# controller11lcd.net
KiCad netlist of a schematic drawn in EAGLE
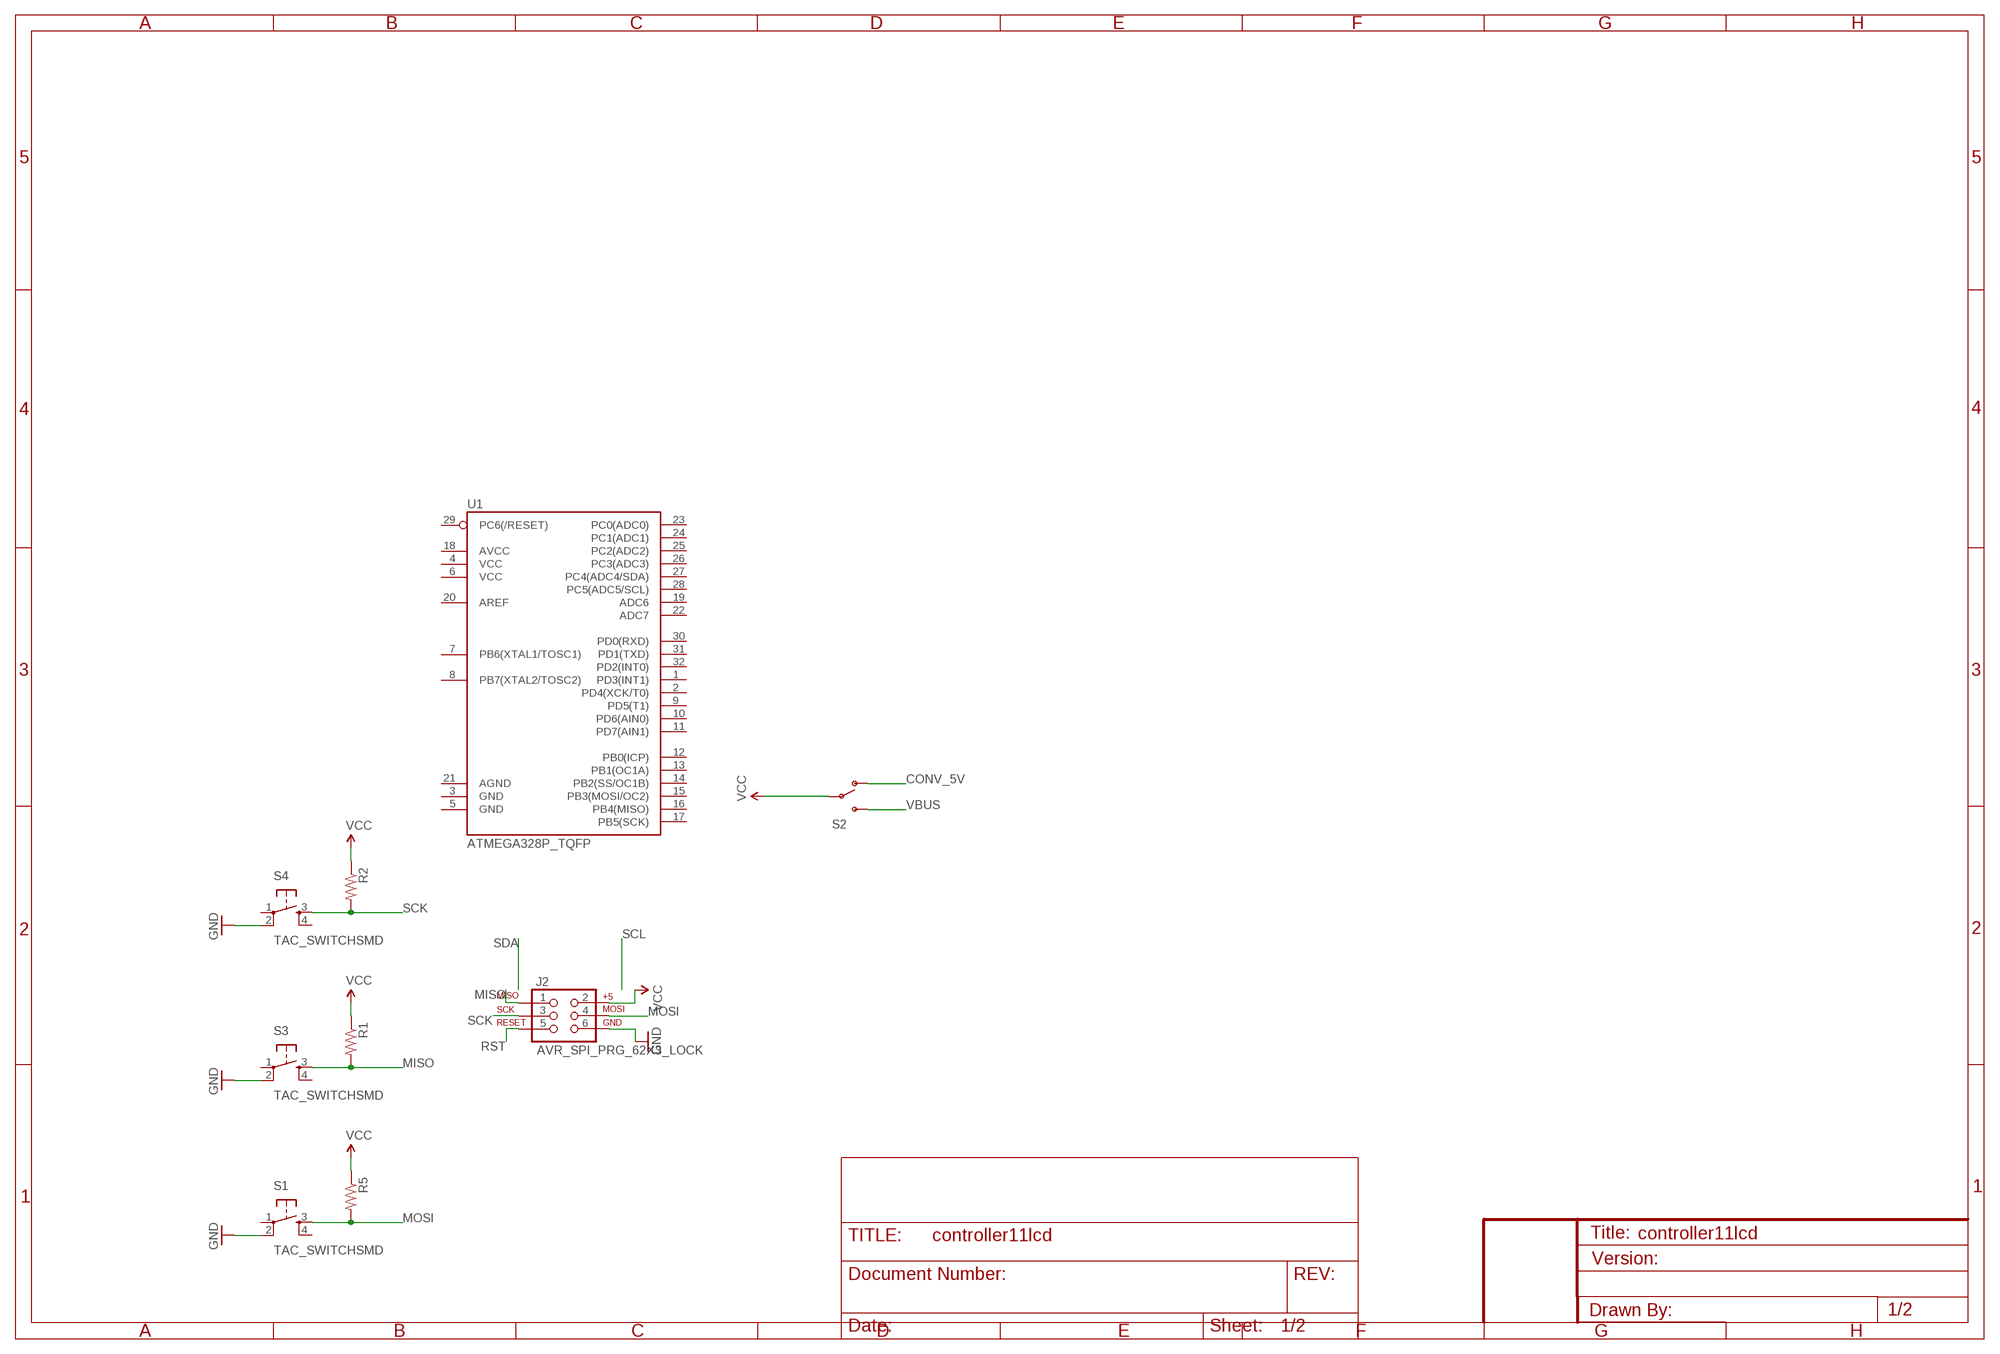
[diagram p0: schematic, sheet 1]
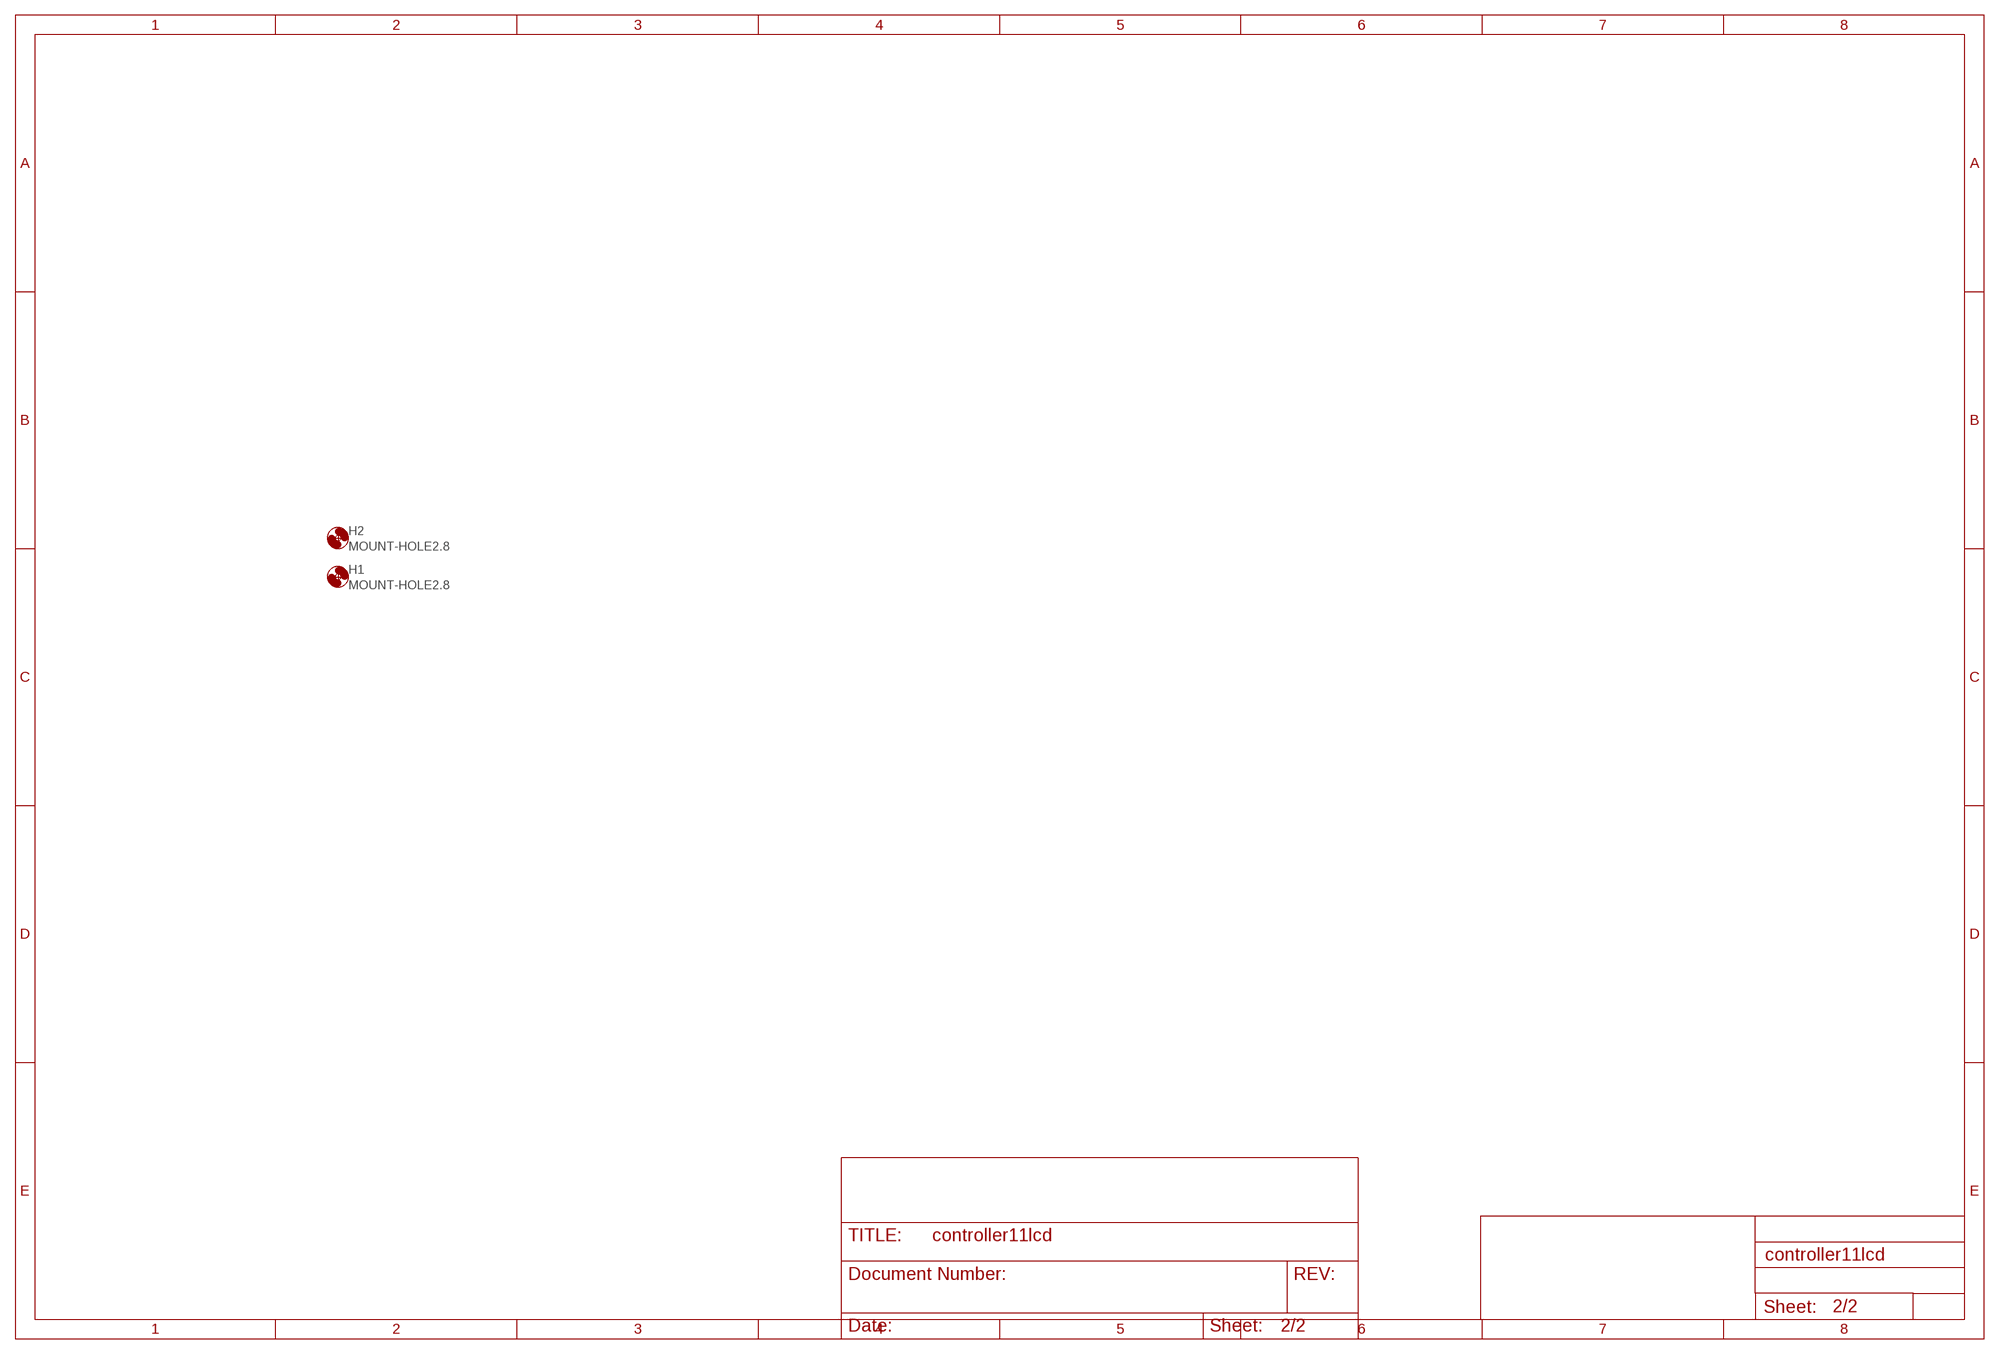
[diagram p1: schematic, sheet 2]

(export (version "E")
  (design (tool "Eeschema 10.0.6"))
  (components
    (comp (ref "H1")
      (value "MOUNT-HOLE2.8")
      (footprint "eagle-import:2,8")
      (libsource (lib "eagle-import") (part "MOUNT-HOLE2.8"))
    )
    (comp (ref "H2")
      (value "MOUNT-HOLE2.8")
      (footprint "eagle-import:2,8")
      (libsource (lib "eagle-import") (part "MOUNT-HOLE2.8"))
    )
    (comp (ref "J2")
      (value "AVR_SPI_PRG_62X3_LOCK")
      (footprint "eagle-import:2X3_LOCK")
      (libsource (lib "eagle-import") (part "AVR_SPI_PRG_62X3_LOCK"))
    )
    (comp (ref "R1")
      (value "RESISTOR1206")
      (footprint "eagle-import:1206")
      (libsource (lib "eagle-import") (part "RESISTOR1206"))
    )
    (comp (ref "R2")
      (value "RESISTOR1206")
      (footprint "eagle-import:1206")
      (libsource (lib "eagle-import") (part "RESISTOR1206"))
    )
    (comp (ref "R5")
      (value "RESISTOR1206")
      (footprint "eagle-import:1206")
      (libsource (lib "eagle-import") (part "RESISTOR1206"))
    )
    (comp (ref "S1")
      (value "TAC_SWITCHSMD")
      (footprint "eagle-import:TACTILE-PTH")
      (libsource (lib "eagle-import") (part "TAC_SWITCHPTH"))
    )
    (comp (ref "S2")
      (value "SWITCH-SPDTSMD2")
      (footprint "eagle-import:SWITCH-SPDT-SMD")
      (libsource (lib "eagle-import") (part "SWITCH-SPDTSMD2"))
    )
    (comp (ref "S3")
      (value "TAC_SWITCHSMD")
      (footprint "eagle-import:TACTILE-PTH")
      (libsource (lib "eagle-import") (part "TAC_SWITCHPTH"))
    )
    (comp (ref "S4")
      (value "TAC_SWITCHSMD")
      (footprint "eagle-import:TACTILE-PTH")
      (libsource (lib "eagle-import") (part "TAC_SWITCHPTH"))
    )
    (comp (ref "U1")
      (value "ATMEGA328P_TQFP")
      (footprint "eagle-import:TQFP32-08")
      (libsource (lib "eagle-import") (part "ATMEGA328P_TQFP"))
    )
  )
  (nets
    (net (code "1") (name "CONV_5V") (class "Default")
      (node (ref "S2") (pin "1") (pinfunction "O_1") (pintype "passive"))
    )
    (net (code "2") (name "GND") (class "Default")
      (node (ref "J2") (pin "6") (pinfunction "6_6") (pintype "passive"))
      (node (ref "S1") (pin "2") (pinfunction "2_2") (pintype "passive"))
      (node (ref "S3") (pin "2") (pinfunction "2_2") (pintype "passive"))
      (node (ref "S4") (pin "2") (pinfunction "2_2") (pintype "passive"))
    )
    (net (code "3") (name "MISO") (class "Default")
      (node (ref "J2") (pin "1") (pinfunction "1_1") (pintype "passive"))
      (node (ref "R1") (pin "2") (pinfunction "2_2") (pintype "passive"))
      (node (ref "S3") (pin "3") (pinfunction "3_3") (pintype "passive"))
    )
    (net (code "4") (name "MOSI") (class "Default")
      (node (ref "J2") (pin "4") (pinfunction "4_4") (pintype "passive"))
      (node (ref "R5") (pin "2") (pinfunction "2_2") (pintype "passive"))
      (node (ref "S1") (pin "3") (pinfunction "3_3") (pintype "passive"))
    )
    (net (code "5") (name "RST") (class "Default")
      (node (ref "J2") (pin "5") (pinfunction "5_5") (pintype "passive"))
    )
    (net (code "6") (name "SCK") (class "Default")
      (node (ref "J2") (pin "3") (pinfunction "3_3") (pintype "passive"))
      (node (ref "R2") (pin "2") (pinfunction "2_2") (pintype "passive"))
      (node (ref "S4") (pin "3") (pinfunction "3_3") (pintype "passive"))
    )
    (net (code "9") (name "VBUS") (class "Default")
      (node (ref "S2") (pin "3") (pinfunction "S_3") (pintype "passive"))
    )
    (net (code "10") (name "VCC") (class "Default")
      (node (ref "J2") (pin "2") (pinfunction "2_2") (pintype "passive"))
      (node (ref "R1") (pin "1") (pinfunction "1_1") (pintype "passive"))
      (node (ref "R2") (pin "1") (pinfunction "1_1") (pintype "passive"))
      (node (ref "R5") (pin "1") (pinfunction "1_1") (pintype "passive"))
      (node (ref "S2") (pin "2") (pinfunction "P_2") (pintype "passive"))
    )
    (net (code "11") (name "unconnected-(S1-Pad1)") (class "Default")
      (node (ref "S1") (pin "1") (pinfunction "1_1") (pintype "passive"))
    )
    (net (code "12") (name "unconnected-(S1-Pad4)") (class "Default")
      (node (ref "S1") (pin "4") (pinfunction "4_4") (pintype "passive"))
    )
    (net (code "13") (name "unconnected-(S3-Pad1)") (class "Default")
      (node (ref "S3") (pin "1") (pinfunction "1_1") (pintype "passive"))
    )
    (net (code "14") (name "unconnected-(S3-Pad4)") (class "Default")
      (node (ref "S3") (pin "4") (pinfunction "4_4") (pintype "passive"))
    )
    (net (code "15") (name "unconnected-(S4-Pad1)") (class "Default")
      (node (ref "S4") (pin "1") (pinfunction "1_1") (pintype "passive"))
    )
    (net (code "16") (name "unconnected-(S4-Pad4)") (class "Default")
      (node (ref "S4") (pin "4") (pinfunction "4_4") (pintype "passive"))
    )
    (net (code "17") (name "unconnected-(U1-ADC6-Pad19)") (class "Default")
      (node (ref "U1") (pin "19") (pinfunction "ADC6_19") (pintype "bidirectional"))
    )
    (net (code "18") (name "unconnected-(U1-ADC7-Pad22)") (class "Default")
      (node (ref "U1") (pin "22") (pinfunction "ADC7_22") (pintype "bidirectional"))
    )
    (net (code "19") (name "unconnected-(U1-AGND-Pad21)") (class "Default")
      (node (ref "U1") (pin "21") (pinfunction "AGND_21") (pintype "bidirectional"))
    )
    (net (code "20") (name "unconnected-(U1-AREF-Pad20)") (class "Default")
      (node (ref "U1") (pin "20") (pinfunction "AREF_20") (pintype "bidirectional"))
    )
    (net (code "21") (name "unconnected-(U1-AVCC-Pad18)") (class "Default")
      (node (ref "U1") (pin "18") (pinfunction "AVCC_18") (pintype "bidirectional"))
    )
    (net (code "22") (name "unconnected-(U1-GND-Pad3)") (class "Default")
      (node (ref "U1") (pin "3") (pinfunction "GND_3") (pintype "bidirectional"))
    )
    (net (code "23") (name "unconnected-(U1-GND-Pad5)") (class "Default")
      (node (ref "U1") (pin "5") (pinfunction "GND_5") (pintype "bidirectional"))
    )
    (net (code "24") (name "unconnected-(U1-PB0(ICP)-Pad12)") (class "Default")
      (node (ref "U1") (pin "12") (pinfunction "PB0(ICP)_12") (pintype "bidirectional"))
    )
    (net (code "25") (name "unconnected-(U1-PB1(OC1A)-Pad13)") (class "Default")
      (node (ref "U1") (pin "13") (pinfunction "PB1(OC1A)_13") (pintype "bidirectional"))
    )
    (net (code "26") (name "unconnected-(U1-PB2(SS{slash}OC1B)-Pad14)") (class "Default")
      (node (ref "U1") (pin "14") (pinfunction "PB2(SS/OC1B)_14") (pintype "bidirectional"))
    )
    (net (code "27") (name "unconnected-(U1-PB3(MOSI{slash}OC2)-Pad15)") (class "Default")
      (node (ref "U1") (pin "15") (pinfunction "PB3(MOSI/OC2)_15") (pintype "bidirectional"))
    )
    (net (code "28") (name "unconnected-(U1-PB4(MISO)-Pad16)") (class "Default")
      (node (ref "U1") (pin "16") (pinfunction "PB4(MISO)_16") (pintype "bidirectional"))
    )
    (net (code "29") (name "unconnected-(U1-PB5(SCK)-Pad17)") (class "Default")
      (node (ref "U1") (pin "17") (pinfunction "PB5(SCK)_17") (pintype "bidirectional"))
    )
    (net (code "30") (name "unconnected-(U1-PB6(XTAL1{slash}TOSC1)-Pad7)") (class "Default")
      (node (ref "U1") (pin "7") (pinfunction "PB6(XTAL1/TOSC1)_7") (pintype "bidirectional"))
    )
    (net (code "31") (name "unconnected-(U1-PB7(XTAL2{slash}TOSC2)-Pad8)") (class "Default")
      (node (ref "U1") (pin "8") (pinfunction "PB7(XTAL2/TOSC2)_8") (pintype "bidirectional"))
    )
    (net (code "32") (name "unconnected-(U1-PC0(ADC0)-Pad23)") (class "Default")
      (node (ref "U1") (pin "23") (pinfunction "PC0(ADC0)_23") (pintype "bidirectional"))
    )
    (net (code "33") (name "unconnected-(U1-PC1(ADC1)-Pad24)") (class "Default")
      (node (ref "U1") (pin "24") (pinfunction "PC1(ADC1)_24") (pintype "bidirectional"))
    )
    (net (code "34") (name "unconnected-(U1-PC2(ADC2)-Pad25)") (class "Default")
      (node (ref "U1") (pin "25") (pinfunction "PC2(ADC2)_25") (pintype "bidirectional"))
    )
    (net (code "35") (name "unconnected-(U1-PC3(ADC3)-Pad26)") (class "Default")
      (node (ref "U1") (pin "26") (pinfunction "PC3(ADC3)_26") (pintype "bidirectional"))
    )
    (net (code "36") (name "unconnected-(U1-PC4(ADC4{slash}SDA)-Pad27)") (class "Default")
      (node (ref "U1") (pin "27") (pinfunction "PC4(ADC4/SDA)_27") (pintype "bidirectional"))
    )
    (net (code "37") (name "unconnected-(U1-PC5(ADC5{slash}SCL)-Pad28)") (class "Default")
      (node (ref "U1") (pin "28") (pinfunction "PC5(ADC5/SCL)_28") (pintype "bidirectional"))
    )
    (net (code "38") (name "unconnected-(U1-PC6({slash}RESET)-Pad29)") (class "Default")
      (node (ref "U1") (pin "29") (pinfunction "PC6(/RESET)_29") (pintype "bidirectional"))
    )
    (net (code "39") (name "unconnected-(U1-PD0(RXD)-Pad30)") (class "Default")
      (node (ref "U1") (pin "30") (pinfunction "PD0(RXD)_30") (pintype "bidirectional"))
    )
    (net (code "40") (name "unconnected-(U1-PD1(TXD)-Pad31)") (class "Default")
      (node (ref "U1") (pin "31") (pinfunction "PD1(TXD)_31") (pintype "bidirectional"))
    )
    (net (code "41") (name "unconnected-(U1-PD2(INT0)-Pad32)") (class "Default")
      (node (ref "U1") (pin "32") (pinfunction "PD2(INT0)_32") (pintype "bidirectional"))
    )
    (net (code "42") (name "unconnected-(U1-PD3(INT1)-Pad1)") (class "Default")
      (node (ref "U1") (pin "1") (pinfunction "PD3(INT1)_1") (pintype "bidirectional"))
    )
    (net (code "43") (name "unconnected-(U1-PD4(XCK{slash}T0)-Pad2)") (class "Default")
      (node (ref "U1") (pin "2") (pinfunction "PD4(XCK/T0)_2") (pintype "bidirectional"))
    )
    (net (code "44") (name "unconnected-(U1-PD5(T1)-Pad9)") (class "Default")
      (node (ref "U1") (pin "9") (pinfunction "PD5(T1)_9") (pintype "bidirectional"))
    )
    (net (code "45") (name "unconnected-(U1-PD6(AIN0)-Pad10)") (class "Default")
      (node (ref "U1") (pin "10") (pinfunction "PD6(AIN0)_10") (pintype "bidirectional"))
    )
    (net (code "46") (name "unconnected-(U1-PD7(AIN1)-Pad11)") (class "Default")
      (node (ref "U1") (pin "11") (pinfunction "PD7(AIN1)_11") (pintype "bidirectional"))
    )
    (net (code "47") (name "unconnected-(U1-VCC-Pad4)") (class "Default")
      (node (ref "U1") (pin "4") (pinfunction "VCC_4") (pintype "bidirectional"))
    )
    (net (code "48") (name "unconnected-(U1-VCC-Pad6)") (class "Default")
      (node (ref "U1") (pin "6") (pinfunction "VCC_6") (pintype "bidirectional"))
    )
  )
)
